# HOLTER_AD.net
KiCad netlist of a schematic drawn in EAGLE
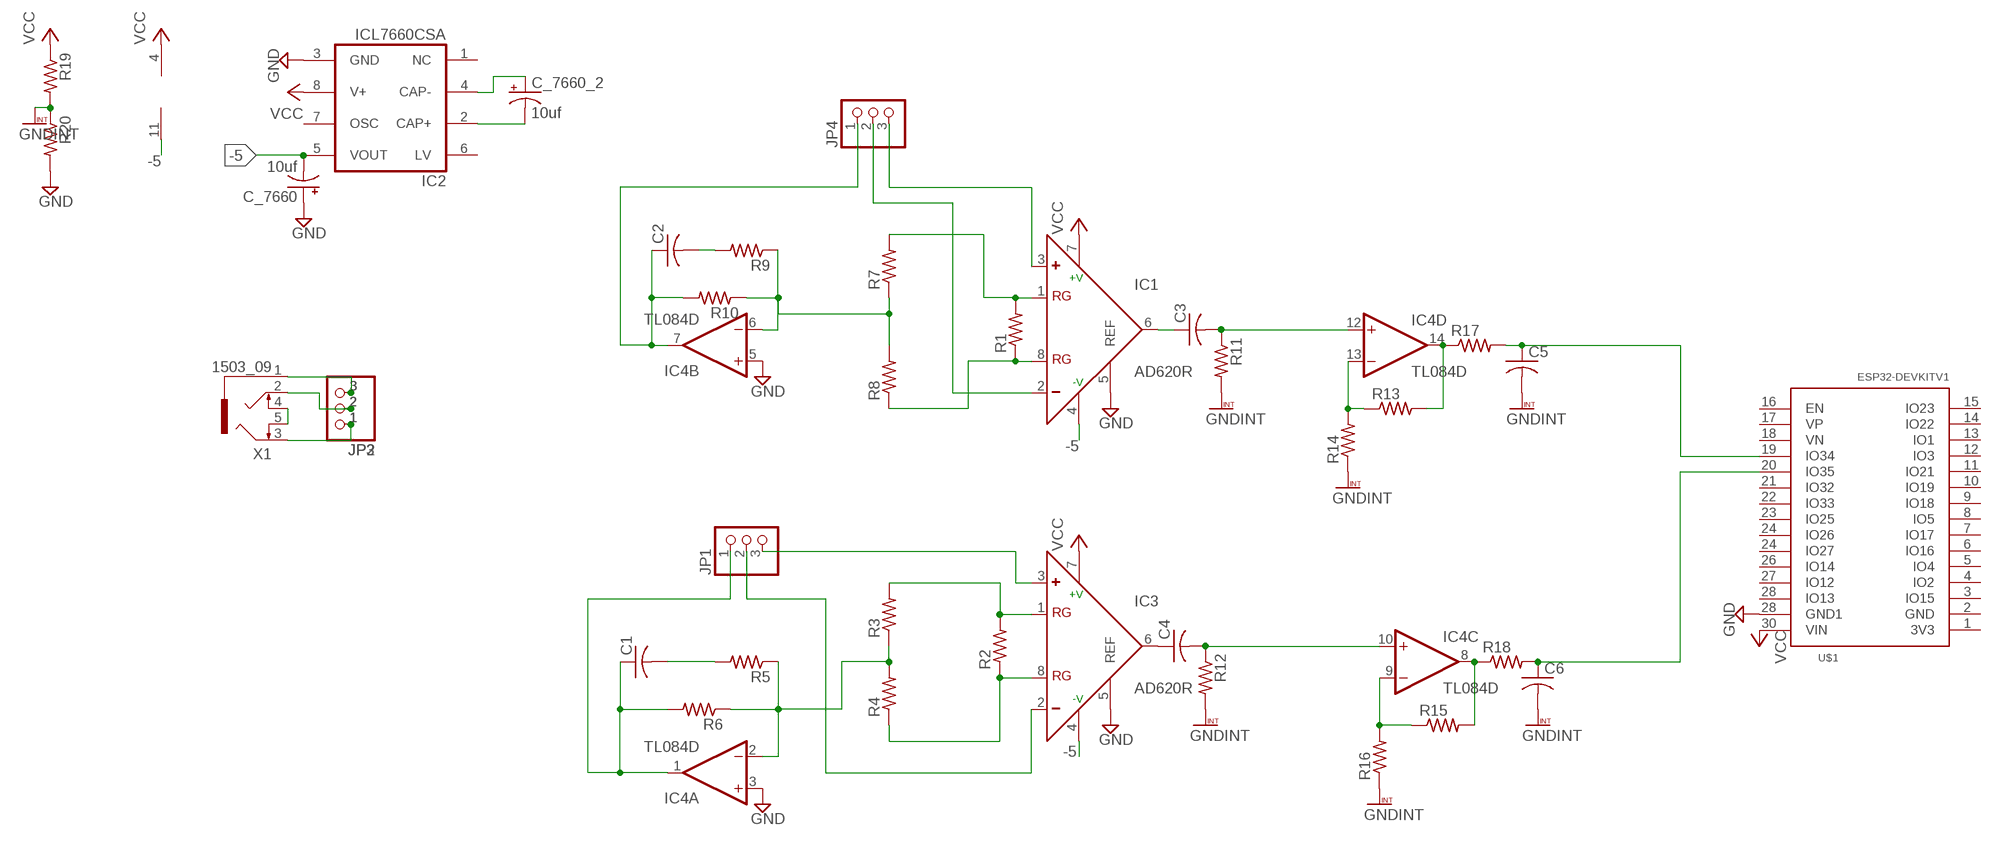
[diagram p0: schematic, sheet 1]

(export (version "E")
  (design (tool "Eeschema 10.0.6"))
  (components
    (comp (ref "C1")
      (value "C-US050-030X075")
      (footprint "eagle-import:C050-030X075")
      (libsource (lib "eagle-import") (part "C-US050-030X075"))
    )
    (comp (ref "C2")
      (value "C-US050-030X075")
      (footprint "eagle-import:C050-030X075")
      (libsource (lib "eagle-import") (part "C-US050-030X075"))
    )
    (comp (ref "C3")
      (value "C-US050-030X075")
      (footprint "eagle-import:C050-030X075")
      (libsource (lib "eagle-import") (part "C-US050-030X075"))
    )
    (comp (ref "C4")
      (value "C-US050-030X075")
      (footprint "eagle-import:C050-030X075")
      (libsource (lib "eagle-import") (part "C-US050-030X075"))
    )
    (comp (ref "C5")
      (value "C-US050-030X075")
      (footprint "eagle-import:C050-030X075")
      (libsource (lib "eagle-import") (part "C-US050-030X075"))
    )
    (comp (ref "C6")
      (value "C-US050-030X075")
      (footprint "eagle-import:C050-030X075")
      (libsource (lib "eagle-import") (part "C-US050-030X075"))
    )
    (comp (ref "C_7660")
      (value "10uf")
      (footprint "eagle-import:E2-5")
      (libsource (lib "eagle-import") (part "CPOL-USE2-5"))
    )
    (comp (ref "C_7660_2")
      (value "10uf")
      (footprint "eagle-import:E2-5")
      (libsource (lib "eagle-import") (part "CPOL-USE2-5"))
    )
    (comp (ref "IC1")
      (value "AD620R")
      (footprint "eagle-import:SO8")
      (fields (field (name "MPN") "AD620AR"))
      (libsource (lib "eagle-import") (part "AD620R"))
    )
    (comp (ref "IC2")
      (value "ICL7660CSA")
      (footprint "eagle-import:SO08")
      (fields (field (name "MF") "MAXIM"))
      (libsource (lib "eagle-import") (part "ICL7660CSA"))
    )
    (comp (ref "IC3")
      (value "AD620R")
      (footprint "eagle-import:SO8")
      (fields (field (name "MPN") "AD620AR"))
      (libsource (lib "eagle-import") (part "AD620R"))
    )
    (comp (ref "IC4")
      (value "TL084D")
      (footprint "eagle-import:SO14")
      (libsource (lib "eagle-import") (part "TL084D"))
    )
    (comp (ref "JP1")
      (value "PINHD-1X3")
      (footprint "eagle-import:1X03")
      (libsource (lib "eagle-import") (part "PINHD-1X3"))
    )
    (comp (ref "JP2")
      (value "PINHD-1X3")
      (footprint "eagle-import:1X03")
      (libsource (lib "eagle-import") (part "PINHD-1X3"))
    )
    (comp (ref "JP3")
      (value "PINHD-1X3")
      (footprint "eagle-import:1X03")
      (libsource (lib "eagle-import") (part "PINHD-1X3"))
    )
    (comp (ref "JP4")
      (value "PINHD-1X3")
      (footprint "eagle-import:1X03")
      (libsource (lib "eagle-import") (part "PINHD-1X3"))
    )
    (comp (ref "R1")
      (value "R-US_0207/10")
      (footprint "eagle-import:0207_10")
      (libsource (lib "eagle-import") (part "R-US_0207/10"))
    )
    (comp (ref "R2")
      (value "R-US_0207/10")
      (footprint "eagle-import:0207_10")
      (libsource (lib "eagle-import") (part "R-US_0207/10"))
    )
    (comp (ref "R3")
      (value "R-US_0207/10")
      (footprint "eagle-import:0207_10")
      (libsource (lib "eagle-import") (part "R-US_0207/10"))
    )
    (comp (ref "R4")
      (value "R-US_0207/10")
      (footprint "eagle-import:0207_10")
      (libsource (lib "eagle-import") (part "R-US_0207/10"))
    )
    (comp (ref "R5")
      (value "R-US_0207/10")
      (footprint "eagle-import:0207_10")
      (libsource (lib "eagle-import") (part "R-US_0207/10"))
    )
    (comp (ref "R6")
      (value "R-US_0207/10")
      (footprint "eagle-import:0207_10")
      (libsource (lib "eagle-import") (part "R-US_0207/10"))
    )
    (comp (ref "R7")
      (value "R-US_0207/10")
      (footprint "eagle-import:0207_10")
      (libsource (lib "eagle-import") (part "R-US_0207/10"))
    )
    (comp (ref "R8")
      (value "R-US_0207/10")
      (footprint "eagle-import:0207_10")
      (libsource (lib "eagle-import") (part "R-US_0207/10"))
    )
    (comp (ref "R9")
      (value "R-US_0207/10")
      (footprint "eagle-import:0207_10")
      (libsource (lib "eagle-import") (part "R-US_0207/10"))
    )
    (comp (ref "R10")
      (value "R-US_0207/10")
      (footprint "eagle-import:0207_10")
      (libsource (lib "eagle-import") (part "R-US_0207/10"))
    )
    (comp (ref "R11")
      (value "R-US_0207/10")
      (footprint "eagle-import:0207_10")
      (libsource (lib "eagle-import") (part "R-US_0207/10"))
    )
    (comp (ref "R12")
      (value "R-US_0207/10")
      (footprint "eagle-import:0207_10")
      (libsource (lib "eagle-import") (part "R-US_0207/10"))
    )
    (comp (ref "R13")
      (value "R-US_0207/10")
      (footprint "eagle-import:0207_10")
      (libsource (lib "eagle-import") (part "R-US_0207/10"))
    )
    (comp (ref "R14")
      (value "R-US_0207/10")
      (footprint "eagle-import:0207_10")
      (libsource (lib "eagle-import") (part "R-US_0207/10"))
    )
    (comp (ref "R15")
      (value "R-US_0207/10")
      (footprint "eagle-import:0207_10")
      (libsource (lib "eagle-import") (part "R-US_0207/10"))
    )
    (comp (ref "R16")
      (value "R-US_0207/10")
      (footprint "eagle-import:0207_10")
      (libsource (lib "eagle-import") (part "R-US_0207/10"))
    )
    (comp (ref "R17")
      (value "R-US_0207/10")
      (footprint "eagle-import:0207_10")
      (libsource (lib "eagle-import") (part "R-US_0207/10"))
    )
    (comp (ref "R18")
      (value "R-US_0207/10")
      (footprint "eagle-import:0207_10")
      (libsource (lib "eagle-import") (part "R-US_0207/10"))
    )
    (comp (ref "R19")
      (value "R-US_0207/10")
      (footprint "eagle-import:0207_10")
      (libsource (lib "eagle-import") (part "R-US_0207/10"))
    )
    (comp (ref "R20")
      (value "R-US_0207/10")
      (footprint "eagle-import:0207_10")
      (libsource (lib "eagle-import") (part "R-US_0207/10"))
    )
    (comp (ref "U$1")
      (value "ESP32DEVKITV1")
      (footprint "eagle-import:ESP32-DEVKITV1")
      (libsource (lib "eagle-import") (part "ESP32DEVKITV1"))
    )
    (comp (ref "X1")
      (value "1503_09")
      (footprint "eagle-import:1503_09")
      (libsource (lib "eagle-import") (part "1503_09"))
    )
  )
  (nets
    (net (code "1") (name "-5") (class "Default")
      (node (ref "C_7660") (pin "-") (pinfunction "-_-") (pintype "passive"))
      (node (ref "IC1") (pin "4") (pinfunction "-V_4") (pintype "power_in"))
      (node (ref "IC2") (pin "5") (pinfunction "VOUT_5") (pintype "output"))
      (node (ref "IC3") (pin "4") (pinfunction "-V_4") (pintype "power_in"))
      (node (ref "IC4") (pin "11") (pinfunction "V-_11") (pintype "power_in"))
    )
    (net (code "2") (name "GND") (class "Default")
      (node (ref "C_7660") (pin "+") (pinfunction "+_+") (pintype "passive"))
      (node (ref "IC1") (pin "5") (pinfunction "REF_5") (pintype "passive"))
      (node (ref "IC2") (pin "3") (pinfunction "GND_3") (pintype "power_in"))
      (node (ref "IC3") (pin "5") (pinfunction "REF_5") (pintype "passive"))
      (node (ref "IC4") (pin "3") (pinfunction "+IN_3") (pintype "input"))
      (node (ref "IC4") (pin "5") (pinfunction "+IN_5") (pintype "input"))
      (node (ref "R20") (pin "2") (pinfunction "2_2") (pintype "passive"))
      (node (ref "U$1") (pin "28") (pinfunction "GND1_28") (pintype "bidirectional"))
    )
    (net (code "3") (name "GNDINT") (class "Default")
      (node (ref "C5") (pin "2") (pinfunction "2_2") (pintype "passive"))
      (node (ref "C6") (pin "2") (pinfunction "2_2") (pintype "passive"))
      (node (ref "R11") (pin "2") (pinfunction "2_2") (pintype "passive"))
      (node (ref "R12") (pin "2") (pinfunction "2_2") (pintype "passive"))
      (node (ref "R14") (pin "1") (pinfunction "1_1") (pintype "passive"))
      (node (ref "R16") (pin "1") (pinfunction "1_1") (pintype "passive"))
      (node (ref "R19") (pin "2") (pinfunction "2_2") (pintype "passive"))
      (node (ref "R20") (pin "1") (pinfunction "1_1") (pintype "passive"))
    )
    (net (code "4") (name "Net-(C1-Pad2)") (class "Default")
      (node (ref "C1") (pin "2") (pinfunction "2_2") (pintype "passive"))
      (node (ref "R5") (pin "2") (pinfunction "2_2") (pintype "passive"))
    )
    (net (code "5") (name "Net-(C2-Pad2)") (class "Default")
      (node (ref "C2") (pin "2") (pinfunction "2_2") (pintype "passive"))
      (node (ref "R9") (pin "2") (pinfunction "2_2") (pintype "passive"))
    )
    (net (code "6") (name "Net-(IC1-+)") (class "Default")
      (node (ref "IC1") (pin "3") (pinfunction "+_3") (pintype "input"))
      (node (ref "JP4") (pin "3") (pinfunction "3_3") (pintype "passive"))
    )
    (net (code "7") (name "Net-(IC1--)") (class "Default")
      (node (ref "IC1") (pin "2") (pinfunction "-_2") (pintype "input"))
      (node (ref "JP4") (pin "2") (pinfunction "2_2") (pintype "passive"))
    )
    (net (code "8") (name "Net-(IC1-OUT)") (class "Default")
      (node (ref "C3") (pin "1") (pinfunction "1_1") (pintype "passive"))
      (node (ref "IC1") (pin "6") (pinfunction "OUT_6") (pintype "output"))
    )
    (net (code "9") (name "Net-(IC1-RG-Pad1)") (class "Default")
      (node (ref "IC1") (pin "1") (pinfunction "RG_1") (pintype "passive"))
      (node (ref "R1") (pin "2") (pinfunction "2_2") (pintype "passive"))
      (node (ref "R7") (pin "2") (pinfunction "2_2") (pintype "passive"))
    )
    (net (code "10") (name "Net-(IC1-RG-Pad8)") (class "Default")
      (node (ref "IC1") (pin "8") (pinfunction "RG_8") (pintype "passive"))
      (node (ref "R1") (pin "1") (pinfunction "1_1") (pintype "passive"))
      (node (ref "R8") (pin "1") (pinfunction "1_1") (pintype "passive"))
    )
    (net (code "11") (name "Net-(IC2-CAP+)") (class "Default")
      (node (ref "C_7660_2") (pin "-") (pinfunction "-_-") (pintype "passive"))
      (node (ref "IC2") (pin "2") (pinfunction "CAP+_2") (pintype "passive"))
    )
    (net (code "12") (name "Net-(IC2-CAP-)") (class "Default")
      (node (ref "C_7660_2") (pin "+") (pinfunction "+_+") (pintype "passive"))
      (node (ref "IC2") (pin "4") (pinfunction "CAP-_4") (pintype "passive"))
    )
    (net (code "13") (name "Net-(IC3-+)") (class "Default")
      (node (ref "IC3") (pin "3") (pinfunction "+_3") (pintype "input"))
      (node (ref "JP1") (pin "3") (pinfunction "3_3") (pintype "passive"))
    )
    (net (code "14") (name "Net-(IC3--)") (class "Default")
      (node (ref "IC3") (pin "2") (pinfunction "-_2") (pintype "input"))
      (node (ref "JP1") (pin "2") (pinfunction "2_2") (pintype "passive"))
    )
    (net (code "15") (name "Net-(IC3-OUT)") (class "Default")
      (node (ref "C4") (pin "1") (pinfunction "1_1") (pintype "passive"))
      (node (ref "IC3") (pin "6") (pinfunction "OUT_6") (pintype "output"))
    )
    (net (code "16") (name "Net-(IC3-RG-Pad1)") (class "Default")
      (node (ref "IC3") (pin "1") (pinfunction "RG_1") (pintype "passive"))
      (node (ref "R2") (pin "2") (pinfunction "2_2") (pintype "passive"))
      (node (ref "R3") (pin "2") (pinfunction "2_2") (pintype "passive"))
    )
    (net (code "17") (name "Net-(IC3-RG-Pad8)") (class "Default")
      (node (ref "IC3") (pin "8") (pinfunction "RG_8") (pintype "passive"))
      (node (ref "R2") (pin "1") (pinfunction "1_1") (pintype "passive"))
      (node (ref "R4") (pin "1") (pinfunction "1_1") (pintype "passive"))
    )
    (net (code "18") (name "Net-(IC4A--IN)") (class "Default")
      (node (ref "IC4") (pin "2") (pinfunction "-IN_2") (pintype "input"))
      (node (ref "R3") (pin "1") (pinfunction "1_1") (pintype "passive"))
      (node (ref "R4") (pin "2") (pinfunction "2_2") (pintype "passive"))
      (node (ref "R5") (pin "1") (pinfunction "1_1") (pintype "passive"))
      (node (ref "R6") (pin "1") (pinfunction "1_1") (pintype "passive"))
    )
    (net (code "19") (name "Net-(IC4A-OUT)") (class "Default")
      (node (ref "C1") (pin "1") (pinfunction "1_1") (pintype "passive"))
      (node (ref "IC4") (pin "1") (pinfunction "OUT_1") (pintype "output"))
      (node (ref "JP1") (pin "1") (pinfunction "1_1") (pintype "passive"))
      (node (ref "R6") (pin "2") (pinfunction "2_2") (pintype "passive"))
    )
    (net (code "20") (name "Net-(IC4B--IN)") (class "Default")
      (node (ref "IC4") (pin "6") (pinfunction "-IN_6") (pintype "input"))
      (node (ref "R10") (pin "1") (pinfunction "1_1") (pintype "passive"))
      (node (ref "R7") (pin "1") (pinfunction "1_1") (pintype "passive"))
      (node (ref "R8") (pin "2") (pinfunction "2_2") (pintype "passive"))
      (node (ref "R9") (pin "1") (pinfunction "1_1") (pintype "passive"))
    )
    (net (code "21") (name "Net-(IC4B-OUT)") (class "Default")
      (node (ref "C2") (pin "1") (pinfunction "1_1") (pintype "passive"))
      (node (ref "IC4") (pin "7") (pinfunction "OUT_7") (pintype "output"))
      (node (ref "JP4") (pin "1") (pinfunction "1_1") (pintype "passive"))
      (node (ref "R10") (pin "2") (pinfunction "2_2") (pintype "passive"))
    )
    (net (code "22") (name "Net-(IC4C-+IN)") (class "Default")
      (node (ref "C4") (pin "2") (pinfunction "2_2") (pintype "passive"))
      (node (ref "IC4") (pin "10") (pinfunction "+IN_10") (pintype "input"))
      (node (ref "R12") (pin "1") (pinfunction "1_1") (pintype "passive"))
    )
    (net (code "23") (name "Net-(IC4C--IN)") (class "Default")
      (node (ref "IC4") (pin "9") (pinfunction "-IN_9") (pintype "input"))
      (node (ref "R15") (pin "1") (pinfunction "1_1") (pintype "passive"))
      (node (ref "R16") (pin "2") (pinfunction "2_2") (pintype "passive"))
    )
    (net (code "24") (name "Net-(IC4C-OUT)") (class "Default")
      (node (ref "IC4") (pin "8") (pinfunction "OUT_8") (pintype "output"))
      (node (ref "R15") (pin "2") (pinfunction "2_2") (pintype "passive"))
      (node (ref "R18") (pin "1") (pinfunction "1_1") (pintype "passive"))
    )
    (net (code "25") (name "Net-(IC4D-+IN)") (class "Default")
      (node (ref "C3") (pin "2") (pinfunction "2_2") (pintype "passive"))
      (node (ref "IC4") (pin "12") (pinfunction "+IN_12") (pintype "input"))
      (node (ref "R11") (pin "1") (pinfunction "1_1") (pintype "passive"))
    )
    (net (code "26") (name "Net-(IC4D--IN)") (class "Default")
      (node (ref "IC4") (pin "13") (pinfunction "-IN_13") (pintype "input"))
      (node (ref "R13") (pin "1") (pinfunction "1_1") (pintype "passive"))
      (node (ref "R14") (pin "2") (pinfunction "2_2") (pintype "passive"))
    )
    (net (code "27") (name "Net-(IC4D-OUT)") (class "Default")
      (node (ref "IC4") (pin "14") (pinfunction "OUT_14") (pintype "output"))
      (node (ref "R13") (pin "2") (pinfunction "2_2") (pintype "passive"))
      (node (ref "R17") (pin "1") (pinfunction "1_1") (pintype "passive"))
    )
    (net (code "28") (name "Net-(JP2-Pad1)") (class "Default")
      (node (ref "JP2") (pin "1") (pinfunction "1_1") (pintype "passive"))
      (node (ref "JP3") (pin "1") (pinfunction "1_1") (pintype "passive"))
      (node (ref "X1") (pin "3") (pinfunction "3_3") (pintype "passive"))
    )
    (net (code "29") (name "Net-(JP2-Pad2)") (class "Default")
      (node (ref "JP2") (pin "2") (pinfunction "2_2") (pintype "passive"))
      (node (ref "JP3") (pin "2") (pinfunction "2_2") (pintype "passive"))
      (node (ref "X1") (pin "2") (pinfunction "2_2") (pintype "passive"))
    )
    (net (code "30") (name "Net-(JP2-Pad3)") (class "Default")
      (node (ref "JP2") (pin "3") (pinfunction "3_3") (pintype "passive"))
      (node (ref "JP3") (pin "3") (pinfunction "3_3") (pintype "passive"))
      (node (ref "X1") (pin "1") (pinfunction "1_1") (pintype "passive"))
    )
    (net (code "31") (name "Net-(U$1-IO34)") (class "Default")
      (node (ref "C5") (pin "1") (pinfunction "1_1") (pintype "passive"))
      (node (ref "R17") (pin "2") (pinfunction "2_2") (pintype "passive"))
      (node (ref "U$1") (pin "19") (pinfunction "IO34_19") (pintype "bidirectional"))
    )
    (net (code "32") (name "Net-(U$1-IO35)") (class "Default")
      (node (ref "C6") (pin "1") (pinfunction "1_1") (pintype "passive"))
      (node (ref "R18") (pin "2") (pinfunction "2_2") (pintype "passive"))
      (node (ref "U$1") (pin "20") (pinfunction "IO35_20") (pintype "bidirectional"))
    )
    (net (code "33") (name "Net-(X1-Pad4)") (class "Default")
      (node (ref "X1") (pin "4") (pinfunction "4_4") (pintype "passive"))
      (node (ref "X1") (pin "5") (pinfunction "5_5") (pintype "passive"))
    )
    (net (code "34") (name "VCC") (class "Default")
      (node (ref "IC1") (pin "7") (pinfunction "+V_7") (pintype "power_in"))
      (node (ref "IC2") (pin "8") (pinfunction "V+_8") (pintype "power_in"))
      (node (ref "IC3") (pin "7") (pinfunction "+V_7") (pintype "power_in"))
      (node (ref "IC4") (pin "4") (pinfunction "V+_4") (pintype "power_in"))
      (node (ref "R19") (pin "1") (pinfunction "1_1") (pintype "passive"))
      (node (ref "U$1") (pin "30") (pinfunction "VIN_30") (pintype "bidirectional"))
    )
    (net (code "35") (name "unconnected-(IC2-LV-Pad6)") (class "Default")
      (node (ref "IC2") (pin "6") (pinfunction "LV_6") (pintype "passive"))
    )
    (net (code "36") (name "unconnected-(IC2-NC-Pad1)") (class "Default")
      (node (ref "IC2") (pin "1") (pinfunction "NC_1") (pintype "no_connect"))
    )
    (net (code "37") (name "unconnected-(IC2-OSC-Pad7)") (class "Default")
      (node (ref "IC2") (pin "7") (pinfunction "OSC_7") (pintype "output"))
    )
    (net (code "38") (name "unconnected-(U$1-3V3-Pad1)") (class "Default")
      (node (ref "U$1") (pin "1") (pinfunction "3V3_1") (pintype "bidirectional"))
    )
    (net (code "39") (name "unconnected-(U$1-EN-Pad16)") (class "Default")
      (node (ref "U$1") (pin "16") (pinfunction "EN_16") (pintype "bidirectional"))
    )
    (net (code "40") (name "unconnected-(U$1-GND-Pad2)") (class "Default")
      (node (ref "U$1") (pin "2") (pinfunction "GND_2") (pintype "bidirectional"))
    )
    (net (code "41") (name "unconnected-(U$1-IO1-Pad13)") (class "Default")
      (node (ref "U$1") (pin "13") (pinfunction "IO1_13") (pintype "bidirectional"))
    )
    (net (code "42") (name "unconnected-(U$1-IO2-Pad4)") (class "Default")
      (node (ref "U$1") (pin "4") (pinfunction "IO2_4") (pintype "bidirectional"))
    )
    (net (code "43") (name "unconnected-(U$1-IO3-Pad12)") (class "Default")
      (node (ref "U$1") (pin "12") (pinfunction "IO3_12") (pintype "bidirectional"))
    )
    (net (code "44") (name "unconnected-(U$1-IO4-Pad5)") (class "Default")
      (node (ref "U$1") (pin "5") (pinfunction "IO4_5") (pintype "bidirectional"))
    )
    (net (code "45") (name "unconnected-(U$1-IO5-Pad8)") (class "Default")
      (node (ref "U$1") (pin "8") (pinfunction "IO5_8") (pintype "bidirectional"))
    )
    (net (code "46") (name "unconnected-(U$1-IO12-Pad27)") (class "Default")
      (node (ref "U$1") (pin "27") (pinfunction "IO12_27") (pintype "bidirectional"))
    )
    (net (code "47") (name "unconnected-(U$1-IO13-Pad28)") (class "Default")
      (node (ref "U$1") (pin "28") (pinfunction "IO13_28") (pintype "bidirectional"))
    )
    (net (code "48") (name "unconnected-(U$1-IO14-Pad26)") (class "Default")
      (node (ref "U$1") (pin "26") (pinfunction "IO14_26") (pintype "bidirectional"))
    )
    (net (code "49") (name "unconnected-(U$1-IO15-Pad3)") (class "Default")
      (node (ref "U$1") (pin "3") (pinfunction "IO15_3") (pintype "bidirectional"))
    )
    (net (code "50") (name "unconnected-(U$1-IO16-Pad6)") (class "Default")
      (node (ref "U$1") (pin "6") (pinfunction "IO16_6") (pintype "bidirectional"))
    )
    (net (code "51") (name "unconnected-(U$1-IO17-Pad7)") (class "Default")
      (node (ref "U$1") (pin "7") (pinfunction "IO17_7") (pintype "bidirectional"))
    )
    (net (code "52") (name "unconnected-(U$1-IO18-Pad9)") (class "Default")
      (node (ref "U$1") (pin "9") (pinfunction "IO18_9") (pintype "bidirectional"))
    )
    (net (code "53") (name "unconnected-(U$1-IO19-Pad10)") (class "Default")
      (node (ref "U$1") (pin "10") (pinfunction "IO19_10") (pintype "bidirectional"))
    )
    (net (code "54") (name "unconnected-(U$1-IO21-Pad11)") (class "Default")
      (node (ref "U$1") (pin "11") (pinfunction "IO21_11") (pintype "bidirectional"))
    )
    (net (code "55") (name "unconnected-(U$1-IO22-Pad14)") (class "Default")
      (node (ref "U$1") (pin "14") (pinfunction "IO22_14") (pintype "bidirectional"))
    )
    (net (code "56") (name "unconnected-(U$1-IO23-Pad15)") (class "Default")
      (node (ref "U$1") (pin "15") (pinfunction "IO23_15") (pintype "bidirectional"))
    )
    (net (code "57") (name "unconnected-(U$1-IO25-Pad23)") (class "Default")
      (node (ref "U$1") (pin "23") (pinfunction "IO25_23") (pintype "bidirectional"))
    )
    (net (code "58") (name "unconnected-(U$1-IO26-Pad24)") (class "Default")
      (node (ref "U$1") (pin "24") (pinfunction "IO26_24") (pintype "bidirectional"))
    )
    (net (code "59") (name "unconnected-(U$1-IO27-Pad24)") (class "Default")
      (node (ref "U$1") (pin "24") (pinfunction "IO27_24") (pintype "bidirectional"))
    )
    (net (code "60") (name "unconnected-(U$1-IO32-Pad21)") (class "Default")
      (node (ref "U$1") (pin "21") (pinfunction "IO32_21") (pintype "bidirectional"))
    )
    (net (code "61") (name "unconnected-(U$1-IO33-Pad22)") (class "Default")
      (node (ref "U$1") (pin "22") (pinfunction "IO33_22") (pintype "bidirectional"))
    )
    (net (code "62") (name "unconnected-(U$1-VN-Pad18)") (class "Default")
      (node (ref "U$1") (pin "18") (pinfunction "VN_18") (pintype "bidirectional"))
    )
    (net (code "63") (name "unconnected-(U$1-VP-Pad17)") (class "Default")
      (node (ref "U$1") (pin "17") (pinfunction "VP_17") (pintype "bidirectional"))
    )
  )
)
